# SAMR21_Xplained_Pro_Antenna.net
KiCad netlist of a schematic drawn in Altium Designer
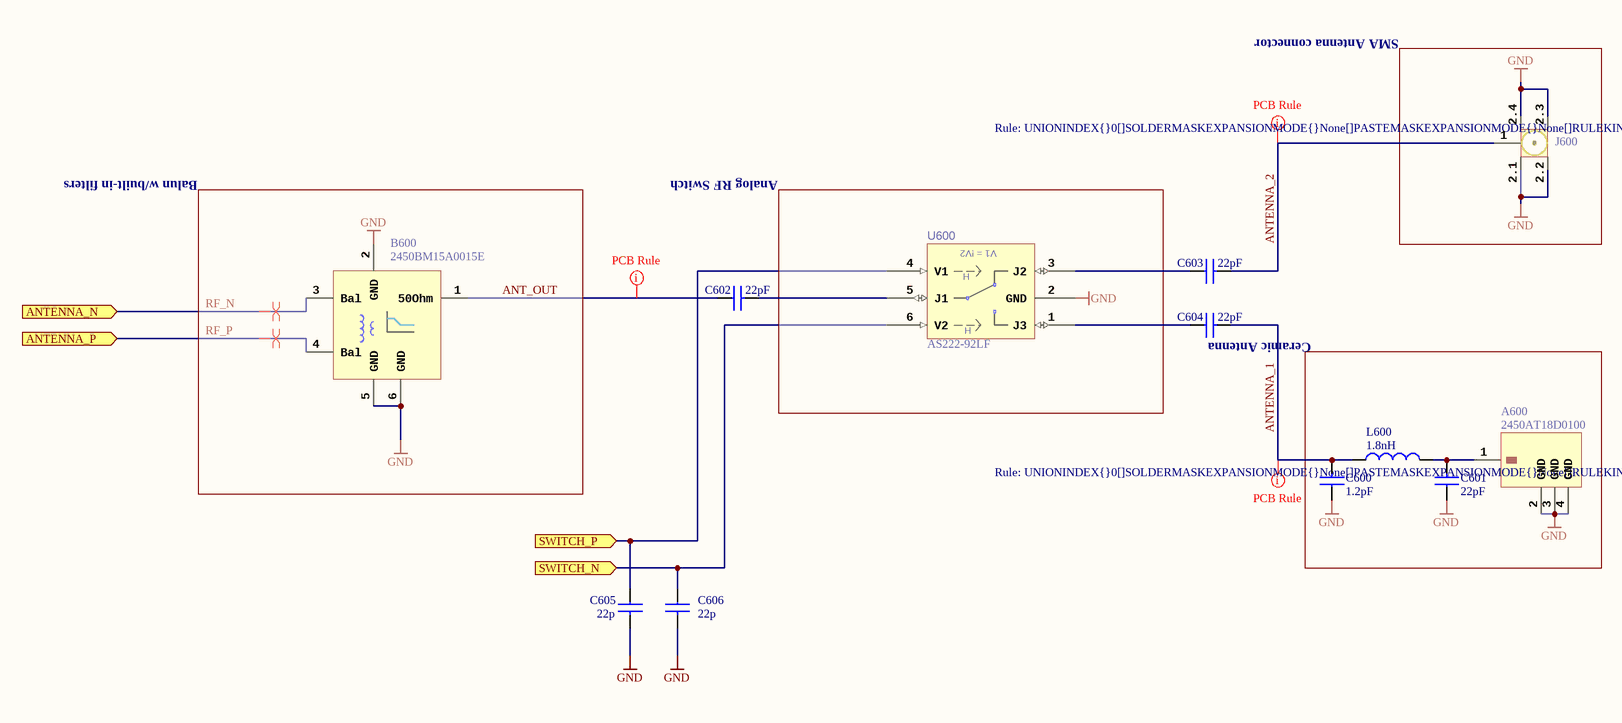
[diagram p0: SAMR21_Xplained_Pro_Antenna.SchDoc]

(export (version "E")
  (design (tool "Eeschema 10.0.6"))
  (components
    (comp (ref "A600")
      (value "2450AT18D0100")
      (footprint "AP8-00678")
      (description "2.45 GHz Ceramic Antenna")
      (fields (field (name "MANUFACTURER") "Johanson Technology") (field (name "Comment") "ANT_CERAMIC_4pin"))
      (libsource (lib "AltiumDbLib") (part "ANT_CERAMIC_4pin"))
    )
    (comp (ref "B600")
      (value "2450BM15A0015E")
      (footprint "AP3-00060")
      (description "Filtered Balun to match AT86RF232/233 (35288)")
      (fields
        (field (name "MANUFACTURER") "Johanson Technology")
        (field (name "Comment") "New part development in cooperation ATMEL/JTI")
      )
      (libsource (lib "AltiumDbLib") (part "FilterBalun_NoFeed"))
    )
    (comp (ref "C600")
      (value "1.2pF")
      (footprint "AP1-00035")
      (description "Ceramic Capacitor, SMD 0201, 25V, NP0, 1.2pF")
      (fields
        (field (name "Comment") "This 1.2pF capacitor is used for RF antennae tuning and can not be replaced by alternatives.")
      )
      (libsource (lib "AltiumDbLib") (part "CAP-NONPOL"))
    )
    (comp (ref "C601")
      (value "22pF")
      (footprint "AP1-00035")
      (description "Ceramic Capacitor, SMD 0201, 25V, NP0, 22PF")
      (fields (field (name "MANUFACTURER") "Johanson Technology") (field (name "MPN") "250R05L220JV4T"))
      (libsource (lib "AltiumDbLib") (part "CAP-NONPOL"))
    )
    (comp (ref "C602")
      (value "22pF")
      (footprint "AP1-00035")
      (description "Ceramic Capacitor, SMD 0201, 25V, NP0, 22PF")
      (fields (field (name "MANUFACTURER") "Johanson Technology") (field (name "MPN") "250R05L220JV4T"))
      (libsource (lib "AltiumDbLib") (part "CAP-NONPOL"))
    )
    (comp (ref "C603")
      (value "22pF")
      (footprint "AP1-00035")
      (description "Ceramic Capacitor, SMD 0201, 25V, NP0, 22PF")
      (fields (field (name "MANUFACTURER") "Johanson Technology") (field (name "MPN") "250R05L220JV4T"))
      (libsource (lib "AltiumDbLib") (part "CAP-NONPOL"))
    )
    (comp (ref "C604")
      (value "22pF")
      (footprint "AP1-00035")
      (description "Ceramic Capacitor, SMD 0201, 25V, NP0, 22PF")
      (fields (field (name "MANUFACTURER") "Johanson Technology") (field (name "MPN") "250R05L220JV4T"))
      (libsource (lib "AltiumDbLib") (part "CAP-NONPOL"))
    )
    (comp (ref "C605")
      (value "22p")
      (footprint "AP1-00001")
      (description "Ceramic capacitor, SMD 0402, NP0, 50V, +/-5%")
      (fields (field (name "TOLERANCE") "50V, +/-5%") (field (name "Comment") "CAP-NONPOL"))
      (libsource (lib "AltiumDbLib") (part "CAP-NONPOL"))
    )
    (comp (ref "C606")
      (value "22p")
      (footprint "AP1-00001")
      (description "Ceramic capacitor, SMD 0402, NP0, 50V, +/-5%")
      (fields (field (name "TOLERANCE") "50V, +/-5%") (field (name "Comment") "CAP-NONPOL"))
      (libsource (lib "AltiumDbLib") (part "CAP-NONPOL"))
    )
    (comp (ref "J600")
      (value "Footprint fits SPC, Tyco and Johnson components footprint")
      (footprint "AP8-00416")
      (description "SMA PCB mounted connector 50Ohm (de19205)")
      (fields (field (name "MANUFACTURER") "Multicomp") (field (name "MPN") "19-46-1-TGG"))
      (libsource (lib "AltiumDbLib") (part "ConnCoax_5pin"))
    )
    (comp (ref "L600")
      (value "1.8nH")
      (footprint "AP2-00028")
      (description "ceramic chip inductor, 1.8nH,0201")
      (fields (field (name "TOLERANCE") "±0.3nH") (field (name "MANUFACTURER") "Johanson Technology"))
      (libsource (lib "AltiumDbLib") (part "INDUCTOR"))
    )
    (comp (ref "U600")
      (value "AS222-92LF")
      (footprint "AP6-00227")
      (description "PHEMT SPDT Analog SWITCH, 0,1-3 GHz")
      (fields (field (name "MANUFACTURER") "SKYWORKS SOLUTIONS") (field (name "Comment") "AS222-92"))
      (libsource (lib "AltiumDbLib") (part "AS222-92"))
    )
  )
  (nets
    (net (code "1") (name "/ANTENNA_1") (class "Default")
      (node (ref "C600") (pin "2") (pinfunction "2_2") (pintype "passive"))
      (node (ref "C604") (pin "2") (pinfunction "2_2") (pintype "passive"))
      (node (ref "L600") (pin "2") (pinfunction "2_2") (pintype "passive"))
    )
    (net (code "2") (name "/ANTENNA_2") (class "Default")
      (node (ref "C603") (pin "2") (pinfunction "2_2") (pintype "passive"))
      (node (ref "J600") (pin "1") (pinfunction "Core_1") (pintype "passive"))
    )
    (net (code "3") (name "/ANT_OUT") (class "Default")
      (node (ref "B600") (pin "1") (pinfunction "50Ohm_1") (pintype "passive"))
      (node (ref "C602") (pin "1") (pinfunction "1_1") (pintype "passive"))
    )
    (net (code "4") (name "/RF_N") (class "Default")
      (node (ref "B600") (pin "3") (pinfunction "Bal_3") (pintype "passive"))
    )
    (net (code "5") (name "/RF_P") (class "Default")
      (node (ref "B600") (pin "4") (pinfunction "Bal_4") (pintype "passive"))
    )
    (net (code "6") (name "/SWITCH_N") (class "Default")
      (node (ref "C606") (pin "1") (pinfunction "1_1") (pintype "passive"))
      (node (ref "U600") (pin "6") (pinfunction "V2_6") (pintype "input"))
    )
    (net (code "7") (name "/SWITCH_P") (class "Default")
      (node (ref "C605") (pin "1") (pinfunction "1_1") (pintype "passive"))
      (node (ref "U600") (pin "4") (pinfunction "V1_4") (pintype "input"))
    )
    (net (code "8") (name "GND") (class "Default")
      (node (ref "A600") (pin "2") (pinfunction "GND_2") (pintype "passive"))
      (node (ref "A600") (pin "3") (pinfunction "GND_3") (pintype "passive"))
      (node (ref "A600") (pin "4") (pinfunction "GND_4") (pintype "passive"))
      (node (ref "B600") (pin "2") (pinfunction "GND_2") (pintype "power_in"))
      (node (ref "B600") (pin "5") (pinfunction "GND_5") (pintype "power_in"))
      (node (ref "B600") (pin "6") (pinfunction "GND_6") (pintype "passive"))
      (node (ref "C600") (pin "1") (pinfunction "1_1") (pintype "passive"))
      (node (ref "C601") (pin "1") (pinfunction "1_1") (pintype "passive"))
      (node (ref "C605") (pin "2") (pinfunction "2_2") (pintype "passive"))
      (node (ref "C606") (pin "2") (pinfunction "2_2") (pintype "passive"))
      (node (ref "J600") (pin "2.1") (pinfunction "GND1_2.1") (pintype "power_in"))
      (node (ref "J600") (pin "2.2") (pinfunction "GND2_2.2") (pintype "power_in"))
      (node (ref "J600") (pin "2.3") (pinfunction "GND3_2.3") (pintype "power_in"))
      (node (ref "J600") (pin "2.4") (pinfunction "GND4_2.4") (pintype "power_in"))
      (node (ref "U600") (pin "2") (pinfunction "GND_2") (pintype "power_in"))
    )
    (net (code "9") (name "Net-(A600-A)") (class "Default")
      (node (ref "A600") (pin "1") (pinfunction "A_1") (pintype "passive"))
      (node (ref "C601") (pin "2") (pinfunction "2_2") (pintype "passive"))
      (node (ref "L600") (pin "1") (pinfunction "1_1") (pintype "passive"))
    )
    (net (code "10") (name "Net-(U600-J1)") (class "Default")
      (node (ref "C602") (pin "2") (pinfunction "2_2") (pintype "passive"))
      (node (ref "U600") (pin "5") (pinfunction "J1_5") (pintype "bidirectional"))
    )
    (net (code "11") (name "Net-(U600-J2)") (class "Default")
      (node (ref "C603") (pin "1") (pinfunction "1_1") (pintype "passive"))
      (node (ref "U600") (pin "3") (pinfunction "J2_3") (pintype "bidirectional"))
    )
    (net (code "12") (name "Net-(U600-J3)") (class "Default")
      (node (ref "C604") (pin "1") (pinfunction "1_1") (pintype "passive"))
      (node (ref "U600") (pin "1") (pinfunction "J3_1") (pintype "bidirectional"))
    )
  )
)
